# RP_INTERFACE_BOARD_V4_1.net
KiCad netlist of a schematic drawn in Altium Designer
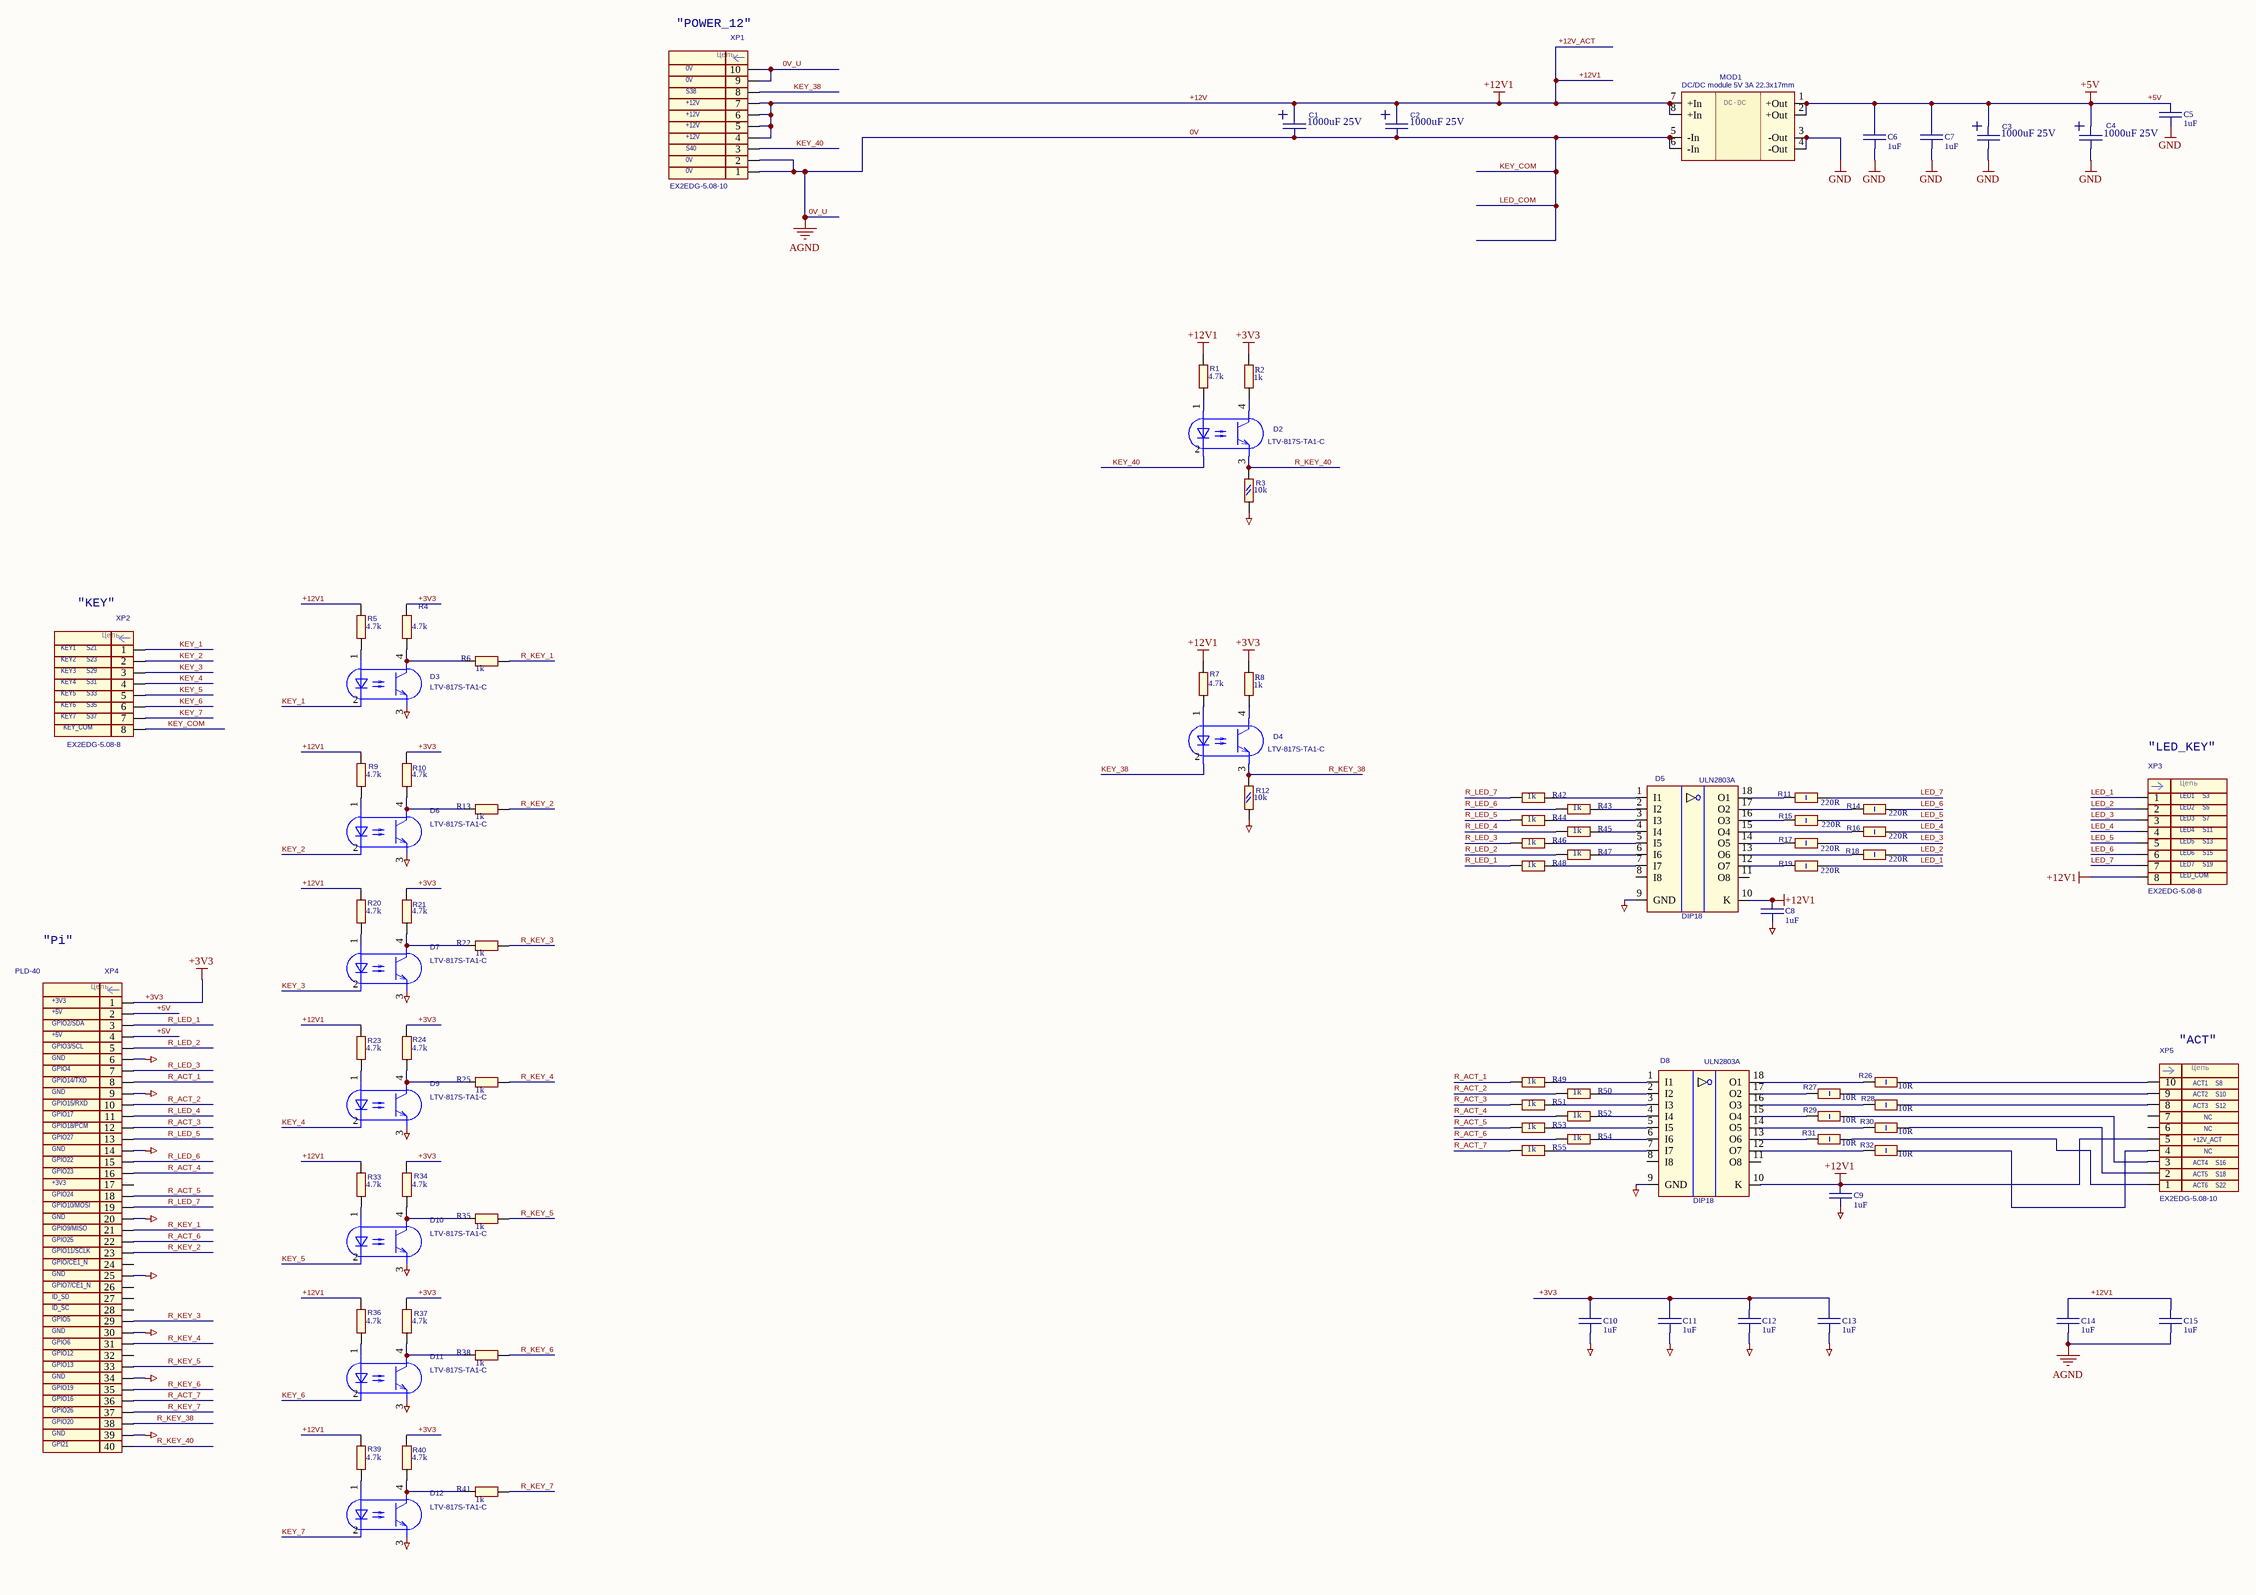
[diagram p0: RP_INTERFACE_BOARD_V4.1.SchDoc]

(export (version "E")
  (design (tool "Eeschema 10.0.6"))
  (components
    (comp (ref "C1")
      (value "EXR102M25B")
      (footprint "RADIAL 13X25")
      (description "1000uF 25V 13x21mm")
      (fields (field (name "ALTIUM_UNNAMED_1") "1000uF 25V"))
      (libsource (lib "*") (part "EXR102M25B"))
    )
    (comp (ref "C2")
      (value "EXR102M25B")
      (footprint "RADIAL 13X25")
      (description "1000uF 25V 13x21mm")
      (fields (field (name "ALTIUM_UNNAMED_1") "1000uF 25V"))
      (libsource (lib "RP_INTERFACE_BOARD") (part "EXR102M25B"))
    )
    (comp (ref "C3")
      (value "EXR102M25B")
      (footprint "RADIAL 13X25")
      (description "1000uF 25V 13x21mm")
      (fields (field (name "ALTIUM_UNNAMED_1") "1000uF 25V"))
      (libsource (lib "RP_INTERFACE_BOARD") (part "EXR102M25B"))
    )
    (comp (ref "C4")
      (value "EXR102M25B")
      (footprint "RADIAL 13X25")
      (description "1000uF 25V 13x21mm")
      (fields (field (name "ALTIUM_UNNAMED_1") "1000uF 25V"))
      (libsource (lib "RP_INTERFACE_BOARD") (part "EXR102M25B"))
    )
    (comp (ref "C5")
      (value "C0805, 1uF, 50V, X7R")
      (footprint "C0805")
      (fields (field (name "ALTIUM_UNNAMED_1") "1uF"))
      (libsource (lib "CAPACITORS") (part "C0805, 1uF, 50V, X7R"))
    )
    (comp (ref "C6")
      (value "C0805, 1uF, 50V, X7R")
      (footprint "C0805")
      (fields (field (name "ALTIUM_UNNAMED_1") "1uF"))
      (libsource (lib "CAPACITORS") (part "C0805, 1uF, 50V, X7R"))
    )
    (comp (ref "C7")
      (value "C0805, 1uF, 50V, X7R")
      (footprint "C0805")
      (fields (field (name "ALTIUM_UNNAMED_1") "1uF"))
      (libsource (lib "CAPACITORS") (part "C0805, 1uF, 50V, X7R"))
    )
    (comp (ref "C8")
      (value "C0805, 1uF, 50V, X7R")
      (footprint "C0805")
      (fields (field (name "ALTIUM_UNNAMED_1") "1uF"))
      (libsource (lib "CAPACITORS") (part "C0805, 1uF, 50V, X7R"))
    )
    (comp (ref "C9")
      (value "C0805, 1uF, 50V, X7R")
      (footprint "C0805")
      (fields (field (name "ALTIUM_UNNAMED_1") "1uF"))
      (libsource (lib "CAPACITORS") (part "C0805, 1uF, 50V, X7R"))
    )
    (comp (ref "C10")
      (value "C0805, 1uF, 50V, X7R")
      (footprint "C0805")
      (fields (field (name "ALTIUM_UNNAMED_1") "1uF"))
      (libsource (lib "CAPACITORS") (part "C0805, 1uF, 50V, X7R"))
    )
    (comp (ref "C11")
      (value "C0805, 1uF, 50V, X7R")
      (footprint "C0805")
      (fields (field (name "ALTIUM_UNNAMED_1") "1uF"))
      (libsource (lib "CAPACITORS") (part "C0805, 1uF, 50V, X7R"))
    )
    (comp (ref "C12")
      (value "C0805, 1uF, 50V, X7R")
      (footprint "C0805")
      (fields (field (name "ALTIUM_UNNAMED_1") "1uF"))
      (libsource (lib "CAPACITORS") (part "C0805, 1uF, 50V, X7R"))
    )
    (comp (ref "C13")
      (value "C0805, 1uF, 50V, X7R")
      (footprint "C0805")
      (fields (field (name "ALTIUM_UNNAMED_1") "1uF"))
      (libsource (lib "CAPACITORS") (part "C0805, 1uF, 50V, X7R"))
    )
    (comp (ref "C14")
      (value "C0805, 1uF, 50V, X7R")
      (footprint "C0805")
      (fields (field (name "ALTIUM_UNNAMED_1") "1uF"))
      (libsource (lib "CAPACITORS") (part "C0805, 1uF, 50V, X7R"))
    )
    (comp (ref "C15")
      (value "C0805, 1uF, 50V, X7R")
      (footprint "C0805")
      (fields (field (name "ALTIUM_UNNAMED_1") "1uF"))
      (libsource (lib "CAPACITORS") (part "C0805, 1uF, 50V, X7R"))
    )
    (comp (ref "D2")
      (value "LTV-817S-TA1-C")
      (footprint "SOIC4")
      (description "Optoisolator Transistor Output 5000Vrms 1 Channel 4-SMD")
      (libsource (lib "RP_INTERFACE_BOARD") (part "LTV-817S-TA1-C"))
    )
    (comp (ref "D3")
      (value "LTV-817S-TA1-C")
      (footprint "SOIC4")
      (description "Optoisolator Transistor Output 5000Vrms 1 Channel 4-SMD")
      (libsource (lib "RP_INTERFACE_BOARD") (part "LTV-817S-TA1-C"))
    )
    (comp (ref "D4")
      (value "LTV-817S-TA1-C")
      (footprint "SOIC4")
      (description "Optoisolator Transistor Output 5000Vrms 1 Channel 4-SMD")
      (libsource (lib "RP_INTERFACE_BOARD") (part "LTV-817S-TA1-C"))
    )
    (comp (ref "D5")
      (value "ULN2803A")
      (footprint "DIP18_DIP762W46P254L2286H533Q18P")
      (description "Eight Darlington array, DIP-18")
      (fields (field (name "KORPUS3") "DIP18"))
      (libsource (lib "RP_INTERFACE_BOARD") (part "ULN2803A"))
    )
    (comp (ref "D6")
      (value "LTV-817S-TA1-C")
      (footprint "SOIC4")
      (description "Optoisolator Transistor Output 5000Vrms 1 Channel 4-SMD")
      (libsource (lib "RP_INTERFACE_BOARD") (part "LTV-817S-TA1-C"))
    )
    (comp (ref "D7")
      (value "LTV-817S-TA1-C")
      (footprint "SOIC4")
      (description "Optoisolator Transistor Output 5000Vrms 1 Channel 4-SMD")
      (libsource (lib "RP_INTERFACE_BOARD") (part "LTV-817S-TA1-C"))
    )
    (comp (ref "D8")
      (value "ULN2803A")
      (footprint "DIP18_DIP762W46P254L2286H533Q18P")
      (description "Eight Darlington array, DIP-18")
      (fields (field (name "KORPUS3") "DIP18"))
      (libsource (lib "RP_INTERFACE_BOARD") (part "ULN2803A"))
    )
    (comp (ref "D9")
      (value "LTV-817S-TA1-C")
      (footprint "SOIC4")
      (description "Optoisolator Transistor Output 5000Vrms 1 Channel 4-SMD")
      (libsource (lib "RP_INTERFACE_BOARD") (part "LTV-817S-TA1-C"))
    )
    (comp (ref "D10")
      (value "LTV-817S-TA1-C")
      (footprint "SOIC4")
      (description "Optoisolator Transistor Output 5000Vrms 1 Channel 4-SMD")
      (libsource (lib "RP_INTERFACE_BOARD") (part "LTV-817S-TA1-C"))
    )
    (comp (ref "D11")
      (value "LTV-817S-TA1-C")
      (footprint "SOIC4")
      (description "Optoisolator Transistor Output 5000Vrms 1 Channel 4-SMD")
      (libsource (lib "RP_INTERFACE_BOARD") (part "LTV-817S-TA1-C"))
    )
    (comp (ref "D12")
      (value "LTV-817S-TA1-C")
      (footprint "SOIC4")
      (description "Optoisolator Transistor Output 5000Vrms 1 Channel 4-SMD")
      (libsource (lib "RP_INTERFACE_BOARD") (part "LTV-817S-TA1-C"))
    )
    (comp (ref "MOD1")
      (value "DC/DC module 5V 3A 22.3x17mm")
      (footprint "DC_DC_module 5V, 17x22.3mm")
      (libsource (lib "*") (part "DC/DC module 5V 3A 22.3x17mm"))
    )
    (comp (ref "R1")
      (value "4.7k")
      (footprint "R0805")
      (description "R0805, 4.7k, 5%")
      (libsource (lib "RP_INTERFACE_BOARD") (part "R0805, 4.7k, 5%"))
    )
    (comp (ref "R2")
      (value "R0805, 1k, 5%")
      (footprint "R0805")
      (fields (field (name "ALTIUM_UNNAMED_1") "1k"))
      (libsource (lib "") (part "R0805, 1k, 5%_1"))
    )
    (comp (ref "R3")
      (value "10k")
      (footprint "R0805")
      (description "R0805, 10k, 5%")
      (libsource (lib "RP_INTERFACE_BOARD") (part "R0805, 10k, 5%"))
    )
    (comp (ref "R4")
      (value "4.7k")
      (footprint "R0805")
      (description "R0805, 4.7k, 5%")
      (libsource (lib "RP_INTERFACE_BOARD") (part "R0805, 4.7k, 5%"))
    )
    (comp (ref "R5")
      (value "4.7k")
      (footprint "R0805")
      (description "R0805, 4.7k, 5%")
      (libsource (lib "RP_INTERFACE_BOARD") (part "R0805, 4.7k, 5%"))
    )
    (comp (ref "R6")
      (value "R0805, 1k, 5%")
      (footprint "R0805")
      (fields (field (name "ALTIUM_UNNAMED_1") "1k"))
      (libsource (lib "RP_INTERFACE_BOARD") (part "R0805, 1k, 5%"))
    )
    (comp (ref "R7")
      (value "4.7k")
      (footprint "R0805")
      (description "R0805, 4.7k, 5%")
      (libsource (lib "RP_INTERFACE_BOARD") (part "R0805, 4.7k, 5%"))
    )
    (comp (ref "R8")
      (value "R0805, 1k, 5%")
      (footprint "R0805")
      (fields (field (name "ALTIUM_UNNAMED_1") "1k"))
      (libsource (lib "") (part "R0805, 1k, 5%_1"))
    )
    (comp (ref "R9")
      (value "4.7k")
      (footprint "R0805")
      (description "R0805, 4.7k, 5%")
      (libsource (lib "RP_INTERFACE_BOARD") (part "R0805, 4.7k, 5%"))
    )
    (comp (ref "R10")
      (value "4.7k")
      (footprint "R0805")
      (description "R0805, 4.7k, 5%")
      (libsource (lib "RP_INTERFACE_BOARD") (part "R0805, 4.7k, 5%"))
    )
    (comp (ref "R11")
      (value "R1206, 220R, 5%")
      (footprint "R1206")
      (fields (field (name "ALTIUM_UNNAMED_1") "220R"))
      (libsource (lib "RP_INTERFACE_BOARD") (part "R1206, 220R, 5%"))
    )
    (comp (ref "R12")
      (value "10k")
      (footprint "R0805")
      (description "R0805, 10k, 5%")
      (libsource (lib "RP_INTERFACE_BOARD") (part "R0805, 10k, 5%"))
    )
    (comp (ref "R13")
      (value "R0805, 1k, 5%")
      (footprint "R0805")
      (fields (field (name "ALTIUM_UNNAMED_1") "1k"))
      (libsource (lib "RP_INTERFACE_BOARD") (part "R0805, 1k, 5%"))
    )
    (comp (ref "R14")
      (value "R1206, 220R, 5%")
      (footprint "R1206")
      (fields (field (name "ALTIUM_UNNAMED_1") "220R"))
      (libsource (lib "RP_INTERFACE_BOARD") (part "R1206, 220R, 5%"))
    )
    (comp (ref "R15")
      (value "R1206, 220R, 5%")
      (footprint "R1206")
      (fields (field (name "ALTIUM_UNNAMED_1") "220R"))
      (libsource (lib "RP_INTERFACE_BOARD") (part "R1206, 220R, 5%"))
    )
    (comp (ref "R16")
      (value "R1206, 220R, 5%")
      (footprint "R1206")
      (fields (field (name "ALTIUM_UNNAMED_1") "220R"))
      (libsource (lib "RP_INTERFACE_BOARD") (part "R1206, 220R, 5%"))
    )
    (comp (ref "R17")
      (value "R1206, 220R, 5%")
      (footprint "R1206")
      (fields (field (name "ALTIUM_UNNAMED_1") "220R"))
      (libsource (lib "RP_INTERFACE_BOARD") (part "R1206, 220R, 5%"))
    )
    (comp (ref "R18")
      (value "R1206, 220R, 5%")
      (footprint "R1206")
      (fields (field (name "ALTIUM_UNNAMED_1") "220R"))
      (libsource (lib "RP_INTERFACE_BOARD") (part "R1206, 220R, 5%"))
    )
    (comp (ref "R19")
      (value "R1206, 220R, 5%")
      (footprint "R1206")
      (fields (field (name "ALTIUM_UNNAMED_1") "220R"))
      (libsource (lib "RP_INTERFACE_BOARD") (part "R1206, 220R, 5%"))
    )
    (comp (ref "R20")
      (value "4.7k")
      (footprint "R0805")
      (description "R0805, 4.7k, 5%")
      (libsource (lib "RP_INTERFACE_BOARD") (part "R0805, 4.7k, 5%"))
    )
    (comp (ref "R21")
      (value "4.7k")
      (footprint "R0805")
      (description "R0805, 4.7k, 5%")
      (libsource (lib "RP_INTERFACE_BOARD") (part "R0805, 4.7k, 5%"))
    )
    (comp (ref "R22")
      (value "R0805, 1k, 5%")
      (footprint "R0805")
      (fields (field (name "ALTIUM_UNNAMED_1") "1k"))
      (libsource (lib "RP_INTERFACE_BOARD") (part "R0805, 1k, 5%"))
    )
    (comp (ref "R23")
      (value "4.7k")
      (footprint "R0805")
      (description "R0805, 4.7k, 5%")
      (libsource (lib "RP_INTERFACE_BOARD") (part "R0805, 4.7k, 5%"))
    )
    (comp (ref "R24")
      (value "4.7k")
      (footprint "R0805")
      (description "R0805, 4.7k, 5%")
      (libsource (lib "RP_INTERFACE_BOARD") (part "R0805, 4.7k, 5%"))
    )
    (comp (ref "R25")
      (value "R0805, 1k, 5%")
      (footprint "R0805")
      (fields (field (name "ALTIUM_UNNAMED_1") "1k"))
      (libsource (lib "RP_INTERFACE_BOARD") (part "R0805, 1k, 5%"))
    )
    (comp (ref "R26")
      (value "R1206, 10R, 5%")
      (footprint "R1206")
      (fields (field (name "ALTIUM_UNNAMED_1") "10R"))
      (libsource (lib "*") (part "R1206, 10R, 5%"))
    )
    (comp (ref "R27")
      (value "R1206, 10R, 5%")
      (footprint "R1206")
      (fields (field (name "ALTIUM_UNNAMED_1") "10R"))
      (libsource (lib "*") (part "R1206, 10R, 5%"))
    )
    (comp (ref "R28")
      (value "R1206, 10R, 5%")
      (footprint "R1206")
      (fields (field (name "ALTIUM_UNNAMED_1") "10R"))
      (libsource (lib "*") (part "R1206, 10R, 5%"))
    )
    (comp (ref "R29")
      (value "R1206, 10R, 5%")
      (footprint "R1206")
      (fields (field (name "ALTIUM_UNNAMED_1") "10R"))
      (libsource (lib "*") (part "R1206, 10R, 5%"))
    )
    (comp (ref "R30")
      (value "R1206, 10R, 5%")
      (footprint "R1206")
      (fields (field (name "ALTIUM_UNNAMED_1") "10R"))
      (libsource (lib "*") (part "R1206, 10R, 5%"))
    )
    (comp (ref "R31")
      (value "R1206, 10R, 5%")
      (footprint "R1206")
      (fields (field (name "ALTIUM_UNNAMED_1") "10R"))
      (libsource (lib "*") (part "R1206, 10R, 5%"))
    )
    (comp (ref "R32")
      (value "R1206, 10R, 5%")
      (footprint "R1206")
      (fields (field (name "ALTIUM_UNNAMED_1") "10R"))
      (libsource (lib "*") (part "R1206, 10R, 5%"))
    )
    (comp (ref "R33")
      (value "4.7k")
      (footprint "R0805")
      (description "R0805, 4.7k, 5%")
      (libsource (lib "RP_INTERFACE_BOARD") (part "R0805, 4.7k, 5%"))
    )
    (comp (ref "R34")
      (value "4.7k")
      (footprint "R0805")
      (description "R0805, 4.7k, 5%")
      (libsource (lib "RP_INTERFACE_BOARD") (part "R0805, 4.7k, 5%"))
    )
    (comp (ref "R35")
      (value "R0805, 1k, 5%")
      (footprint "R0805")
      (fields (field (name "ALTIUM_UNNAMED_1") "1k"))
      (libsource (lib "RP_INTERFACE_BOARD") (part "R0805, 1k, 5%"))
    )
    (comp (ref "R36")
      (value "4.7k")
      (footprint "R0805")
      (description "R0805, 4.7k, 5%")
      (libsource (lib "RP_INTERFACE_BOARD") (part "R0805, 4.7k, 5%"))
    )
    (comp (ref "R37")
      (value "4.7k")
      (footprint "R0805")
      (description "R0805, 4.7k, 5%")
      (libsource (lib "RP_INTERFACE_BOARD") (part "R0805, 4.7k, 5%"))
    )
    (comp (ref "R38")
      (value "R0805, 1k, 5%")
      (footprint "R0805")
      (fields (field (name "ALTIUM_UNNAMED_1") "1k"))
      (libsource (lib "RP_INTERFACE_BOARD") (part "R0805, 1k, 5%"))
    )
    (comp (ref "R39")
      (value "4.7k")
      (footprint "R0805")
      (description "R0805, 4.7k, 5%")
      (libsource (lib "RP_INTERFACE_BOARD") (part "R0805, 4.7k, 5%"))
    )
    (comp (ref "R40")
      (value "4.7k")
      (footprint "R0805")
      (description "R0805, 4.7k, 5%")
      (libsource (lib "RP_INTERFACE_BOARD") (part "R0805, 4.7k, 5%"))
    )
    (comp (ref "R41")
      (value "R0805, 1k, 5%")
      (footprint "R0805")
      (fields (field (name "ALTIUM_UNNAMED_1") "1k"))
      (libsource (lib "RP_INTERFACE_BOARD") (part "R0805, 1k, 5%"))
    )
    (comp (ref "R42")
      (value "R0805, 1k, 5%")
      (footprint "R0805")
      (fields (field (name "ALTIUM_UNNAMED_1") "1k"))
      (libsource (lib "RP_INTERFACE_BOARD") (part "R0805, 1k, 5%"))
    )
    (comp (ref "R43")
      (value "R0805, 1k, 5%")
      (footprint "R0805")
      (fields (field (name "ALTIUM_UNNAMED_1") "1k"))
      (libsource (lib "RP_INTERFACE_BOARD") (part "R0805, 1k, 5%"))
    )
    (comp (ref "R44")
      (value "R0805, 1k, 5%")
      (footprint "R0805")
      (fields (field (name "ALTIUM_UNNAMED_1") "1k"))
      (libsource (lib "RP_INTERFACE_BOARD") (part "R0805, 1k, 5%"))
    )
    (comp (ref "R45")
      (value "R0805, 1k, 5%")
      (footprint "R0805")
      (fields (field (name "ALTIUM_UNNAMED_1") "1k"))
      (libsource (lib "RP_INTERFACE_BOARD") (part "R0805, 1k, 5%"))
    )
    (comp (ref "R46")
      (value "R0805, 1k, 5%")
      (footprint "R0805")
      (fields (field (name "ALTIUM_UNNAMED_1") "1k"))
      (libsource (lib "RP_INTERFACE_BOARD") (part "R0805, 1k, 5%"))
    )
    (comp (ref "R47")
      (value "R0805, 1k, 5%")
      (footprint "R0805")
      (fields (field (name "ALTIUM_UNNAMED_1") "1k"))
      (libsource (lib "RP_INTERFACE_BOARD") (part "R0805, 1k, 5%"))
    )
    (comp (ref "R48")
      (value "R0805, 1k, 5%")
      (footprint "R0805")
      (fields (field (name "ALTIUM_UNNAMED_1") "1k"))
      (libsource (lib "RP_INTERFACE_BOARD") (part "R0805, 1k, 5%"))
    )
    (comp (ref "R49")
      (value "R0805, 1k, 5%")
      (footprint "R0805")
      (fields (field (name "ALTIUM_UNNAMED_1") "1k"))
      (libsource (lib "RP_INTERFACE_BOARD") (part "R0805, 1k, 5%"))
    )
    (comp (ref "R50")
      (value "R0805, 1k, 5%")
      (footprint "R0805")
      (fields (field (name "ALTIUM_UNNAMED_1") "1k"))
      (libsource (lib "RP_INTERFACE_BOARD") (part "R0805, 1k, 5%"))
    )
    (comp (ref "R51")
      (value "R0805, 1k, 5%")
      (footprint "R0805")
      (fields (field (name "ALTIUM_UNNAMED_1") "1k"))
      (libsource (lib "RP_INTERFACE_BOARD") (part "R0805, 1k, 5%"))
    )
    (comp (ref "R52")
      (value "R0805, 1k, 5%")
      (footprint "R0805")
      (fields (field (name "ALTIUM_UNNAMED_1") "1k"))
      (libsource (lib "RP_INTERFACE_BOARD") (part "R0805, 1k, 5%"))
    )
    (comp (ref "R53")
      (value "R0805, 1k, 5%")
      (footprint "R0805")
      (fields (field (name "ALTIUM_UNNAMED_1") "1k"))
      (libsource (lib "RP_INTERFACE_BOARD") (part "R0805, 1k, 5%"))
    )
    (comp (ref "R54")
      (value "R0805, 1k, 5%")
      (footprint "R0805")
      (fields (field (name "ALTIUM_UNNAMED_1") "1k"))
      (libsource (lib "RP_INTERFACE_BOARD") (part "R0805, 1k, 5%"))
    )
    (comp (ref "R55")
      (value "R0805, 1k, 5%")
      (footprint "R0805")
      (fields (field (name "ALTIUM_UNNAMED_1") "1k"))
      (libsource (lib "RP_INTERFACE_BOARD") (part "R0805, 1k, 5%"))
    )
    (comp (ref "XP1")
      (value "EX2EDG-5.08-10")
      (footprint "5P08-10N")
      (libsource (lib "") (part "EX2EDG-5_0.08-10_1"))
    )
    (comp (ref "XP2")
      (value "EX2EDG-5.08-8")
      (footprint "5P08-8N")
      (libsource (lib "*") (part "EX2EDG-5.08-8"))
    )
    (comp (ref "XP3")
      (value "EX2EDG-5.08-8")
      (footprint "5P08-8N")
      (libsource (lib "") (part "EX2EDG-5.08-8_1"))
    )
    (comp (ref "XP4")
      (value "PLD-40")
      (footprint "PLD-40")
      (description "PLD-40, вилка штыревая 2.54мм 2x20 прямая")
      (libsource (lib "*") (part "PLD-40"))
    )
    (comp (ref "XP5")
      (value "EX2EDG-5.08-10")
      (footprint "5P08-10N")
      (libsource (lib "*") (part "EX2EDG-5_0.08-10"))
    )
  )
  (nets
    (net (code "1") (name "+3V3") (class "Default")
      (node (ref "C10") (pin "1") (pintype "passive"))
      (node (ref "C11") (pin "1") (pintype "passive"))
      (node (ref "C12") (pin "1") (pintype "passive"))
      (node (ref "C13") (pin "1") (pintype "passive"))
      (node (ref "R10") (pin "1") (pinfunction "1_1") (pintype "passive"))
      (node (ref "R2") (pin "1") (pinfunction "1_1") (pintype "passive"))
      (node (ref "R21") (pin "1") (pinfunction "1_1") (pintype "passive"))
      (node (ref "R24") (pin "1") (pinfunction "1_1") (pintype "passive"))
      (node (ref "R34") (pin "1") (pinfunction "1_1") (pintype "passive"))
      (node (ref "R37") (pin "1") (pinfunction "1_1") (pintype "passive"))
      (node (ref "R4") (pin "1") (pinfunction "1_1") (pintype "passive"))
      (node (ref "R40") (pin "1") (pinfunction "1_1") (pintype "passive"))
      (node (ref "R8") (pin "1") (pinfunction "1_1") (pintype "passive"))
      (node (ref "XP4") (pin "1") (pinfunction "1_1") (pintype "passive"))
    )
    (net (code "2") (name "+5V") (class "Default")
      (node (ref "C3") (pin "2") (pintype "passive"))
      (node (ref "C4") (pin "2") (pintype "passive"))
      (node (ref "C5") (pin "1") (pintype "passive"))
      (node (ref "C6") (pin "1") (pintype "passive"))
      (node (ref "C7") (pin "1") (pintype "passive"))
      (node (ref "MOD1") (pin "1") (pinfunction "+Out_1") (pintype "power_in"))
      (node (ref "MOD1") (pin "2") (pinfunction "+Out_2") (pintype "power_in"))
      (node (ref "XP4") (pin "2") (pinfunction "2_2") (pintype "passive"))
      (node (ref "XP4") (pin "4") (pinfunction "4_4") (pintype "passive"))
    )
    (net (code "3") (name "+12V1") (class "Default")
      (node (ref "C1") (pin "2") (pintype "passive"))
      (node (ref "C14") (pin "1") (pintype "passive"))
      (node (ref "C15") (pin "1") (pintype "passive"))
      (node (ref "C2") (pin "2") (pintype "passive"))
      (node (ref "C8") (pin "1") (pintype "passive"))
      (node (ref "C9") (pin "1") (pintype "passive"))
      (node (ref "D5") (pin "10") (pinfunction "K_10") (pintype "power_in"))
      (node (ref "D8") (pin "10") (pinfunction "K_10") (pintype "power_in"))
      (node (ref "MOD1") (pin "7") (pinfunction "+In_7") (pintype "power_in"))
      (node (ref "MOD1") (pin "8") (pinfunction "+In_8") (pintype "power_in"))
      (node (ref "R1") (pin "1") (pinfunction "1_1") (pintype "passive"))
      (node (ref "R20") (pin "1") (pinfunction "1_1") (pintype "passive"))
      (node (ref "R23") (pin "1") (pinfunction "1_1") (pintype "passive"))
      (node (ref "R33") (pin "1") (pinfunction "1_1") (pintype "passive"))
      (node (ref "R36") (pin "1") (pinfunction "1_1") (pintype "passive"))
      (node (ref "R39") (pin "1") (pinfunction "1_1") (pintype "passive"))
      (node (ref "R5") (pin "1") (pinfunction "1_1") (pintype "passive"))
      (node (ref "R7") (pin "1") (pinfunction "1_1") (pintype "passive"))
      (node (ref "R9") (pin "1") (pinfunction "1_1") (pintype "passive"))
      (node (ref "XP1") (pin "4") (pinfunction "4_4") (pintype "passive"))
      (node (ref "XP1") (pin "5") (pinfunction "5_5") (pintype "passive"))
      (node (ref "XP1") (pin "6") (pinfunction "6_6") (pintype "passive"))
      (node (ref "XP1") (pin "7") (pinfunction "7_7") (pintype "passive"))
      (node (ref "XP3") (pin "8") (pinfunction "8_8") (pintype "passive"))
      (node (ref "XP5") (pin "5") (pinfunction "5_5") (pintype "passive"))
    )
    (net (code "4") (name "/KEY_1") (class "Default")
      (node (ref "D3") (pin "2") (pinfunction "2_2") (pintype "passive"))
      (node (ref "XP2") (pin "1") (pinfunction "1_1") (pintype "passive"))
    )
    (net (code "5") (name "/KEY_2") (class "Default")
      (node (ref "D6") (pin "2") (pinfunction "2_2") (pintype "passive"))
      (node (ref "XP2") (pin "2") (pinfunction "2_2") (pintype "passive"))
    )
    (net (code "6") (name "/KEY_3") (class "Default")
      (node (ref "D7") (pin "2") (pinfunction "2_2") (pintype "passive"))
      (node (ref "XP2") (pin "3") (pinfunction "3_3") (pintype "passive"))
    )
    (net (code "7") (name "/KEY_4") (class "Default")
      (node (ref "D9") (pin "2") (pinfunction "2_2") (pintype "passive"))
      (node (ref "XP2") (pin "4") (pinfunction "4_4") (pintype "passive"))
    )
    (net (code "8") (name "/KEY_5") (class "Default")
      (node (ref "D10") (pin "2") (pinfunction "2_2") (pintype "passive"))
      (node (ref "XP2") (pin "5") (pinfunction "5_5") (pintype "passive"))
    )
    (net (code "9") (name "/KEY_6") (class "Default")
      (node (ref "D11") (pin "2") (pinfunction "2_2") (pintype "passive"))
      (node (ref "XP2") (pin "6") (pinfunction "6_6") (pintype "passive"))
    )
    (net (code "10") (name "/KEY_7") (class "Default")
      (node (ref "D12") (pin "2") (pinfunction "2_2") (pintype "passive"))
      (node (ref "XP2") (pin "7") (pinfunction "7_7") (pintype "passive"))
    )
    (net (code "11") (name "/KEY_38") (class "Default")
      (node (ref "D4") (pin "2") (pinfunction "2_2") (pintype "passive"))
      (node (ref "XP1") (pin "8") (pinfunction "8_8") (pintype "passive"))
    )
    (net (code "12") (name "/KEY_40") (class "Default")
      (node (ref "D2") (pin "2") (pinfunction "2_2") (pintype "passive"))
      (node (ref "XP1") (pin "3") (pinfunction "3_3") (pintype "passive"))
    )
    (net (code "13") (name "/LED_1") (class "Default")
      (node (ref "R19") (pin "2") (pinfunction "2_2") (pintype "passive"))
      (node (ref "XP3") (pin "1") (pinfunction "1_1") (pintype "passive"))
    )
    (net (code "14") (name "/LED_2") (class "Default")
      (node (ref "R18") (pin "2") (pinfunction "2_2") (pintype "passive"))
      (node (ref "XP3") (pin "2") (pinfunction "2_2") (pintype "passive"))
    )
    (net (code "15") (name "/LED_3") (class "Default")
      (node (ref "R17") (pin "2") (pinfunction "2_2") (pintype "passive"))
      (node (ref "XP3") (pin "3") (pinfunction "3_3") (pintype "passive"))
    )
    (net (code "16") (name "/LED_4") (class "Default")
      (node (ref "R16") (pin "2") (pinfunction "2_2") (pintype "passive"))
      (node (ref "XP3") (pin "4") (pinfunction "4_4") (pintype "passive"))
    )
    (net (code "17") (name "/LED_5") (class "Default")
      (node (ref "R15") (pin "2") (pinfunction "2_2") (pintype "passive"))
      (node (ref "XP3") (pin "5") (pinfunction "5_5") (pintype "passive"))
    )
    (net (code "18") (name "/LED_6") (class "Default")
      (node (ref "R14") (pin "2") (pinfunction "2_2") (pintype "passive"))
      (node (ref "XP3") (pin "6") (pinfunction "6_6") (pintype "passive"))
    )
    (net (code "19") (name "/LED_7") (class "Default")
      (node (ref "R11") (pin "2") (pinfunction "2_2") (pintype "passive"))
      (node (ref "XP3") (pin "7") (pinfunction "7_7") (pintype "passive"))
    )
    (net (code "20") (name "/R_ACT_1") (class "Default")
      (node (ref "R49") (pin "2") (pinfunction "2_2") (pintype "passive"))
      (node (ref "XP4") (pin "8") (pinfunction "8_8") (pintype "passive"))
    )
    (net (code "21") (name "/R_ACT_2") (class "Default")
      (node (ref "R50") (pin "2") (pinfunction "2_2") (pintype "passive"))
      (node (ref "XP4") (pin "10") (pinfunction "10_10") (pintype "passive"))
    )
    (net (code "22") (name "/R_ACT_3") (class "Default")
      (node (ref "R51") (pin "2") (pinfunction "2_2") (pintype "passive"))
      (node (ref "XP4") (pin "12") (pinfunction "12_12") (pintype "passive"))
    )
    (net (code "23") (name "/R_ACT_4") (class "Default")
      (node (ref "R52") (pin "2") (pinfunction "2_2") (pintype "passive"))
      (node (ref "XP4") (pin "16") (pinfunction "16_16") (pintype "passive"))
    )
    (net (code "24") (name "/R_ACT_5") (class "Default")
      (node (ref "R53") (pin "2") (pinfunction "2_2") (pintype "passive"))
      (node (ref "XP4") (pin "18") (pinfunction "18_18") (pintype "passive"))
    )
    (net (code "25") (name "/R_ACT_6") (class "Default")
      (node (ref "R54") (pin "2") (pinfunction "2_2") (pintype "passive"))
      (node (ref "XP4") (pin "22") (pinfunction "22_22") (pintype "passive"))
    )
    (net (code "26") (name "/R_ACT_7") (class "Default")
      (node (ref "R55") (pin "2") (pinfunction "2_2") (pintype "passive"))
      (node (ref "XP4") (pin "36") (pinfunction "36_36") (pintype "passive"))
    )
    (net (code "27") (name "/R_KEY_1") (class "Default")
      (node (ref "R6") (pin "1") (pinfunction "1_1") (pintype "passive"))
      (node (ref "XP4") (pin "21") (pinfunction "21_21") (pintype "passive"))
    )
    (net (code "28") (name "/R_KEY_2") (class "Default")
      (node (ref "R13") (pin "1") (pinfunction "1_1") (pintype "passive"))
      (node (ref "XP4") (pin "23") (pinfunction "23_23") (pintype "passive"))
    )
    (net (code "29") (name "/R_KEY_3") (class "Default")
      (node (ref "R22") (pin "1") (pinfunction "1_1") (pintype "passive"))
      (node (ref "XP4") (pin "29") (pinfunction "29_29") (pintype "passive"))
    )
    (net (code "30") (name "/R_KEY_4") (class "Default")
      (node (ref "R25") (pin "1") (pinfunction "1_1") (pintype "passive"))
      (node (ref "XP4") (pin "31") (pinfunction "31_31") (pintype "passive"))
    )
    (net (code "31") (name "/R_KEY_5") (class "Default")
      (node (ref "R35") (pin "1") (pinfunction "1_1") (pintype "passive"))
      (node (ref "XP4") (pin "33") (pinfunction "33_33") (pintype "passive"))
    )
    (net (code "32") (name "/R_KEY_6") (class "Default")
      (node (ref "R38") (pin "1") (pinfunction "1_1") (pintype "passive"))
      (node (ref "XP4") (pin "35") (pinfunction "35_35") (pintype "passive"))
    )
    (net (code "33") (name "/R_KEY_7") (class "Default")
      (node (ref "R41") (pin "1") (pinfunction "1_1") (pintype "passive"))
      (node (ref "XP4") (pin "37") (pinfunction "37_37") (pintype "passive"))
    )
    (net (code "34") (name "/R_KEY_38") (class "Default")
      (node (ref "D4") (pin "3") (pinfunction "3_3") (pintype "passive"))
      (node (ref "R12") (pin "1") (pinfunction "1_1") (pintype "passive"))
      (node (ref "XP4") (pin "38") (pinfunction "38_38") (pintype "passive"))
    )
    (net (code "35") (name "/R_KEY_40") (class "Default")
      (node (ref "D2") (pin "3") (pinfunction "3_3") (pintype "passive"))
      (node (ref "R3") (pin "1") (pinfunction "1_1") (pintype "passive"))
      (node (ref "XP4") (pin "40") (pinfunction "40_40") (pintype "passive"))
    )
    (net (code "36") (name "/R_LED_1") (class "Default")
      (node (ref "R48") (pin "2") (pinfunction "2_2") (pintype "passive"))
      (node (ref "XP4") (pin "3") (pinfunction "3_3") (pintype "passive"))
    )
    (net (code "37") (name "/R_LED_2") (class "Default")
      (node (ref "R47") (pin "2") (pinfunction "2_2") (pintype "passive"))
      (node (ref "XP4") (pin "5") (pinfunction "5_5") (pintype "passive"))
    )
    (net (code "38") (name "/R_LED_3") (class "Default")
      (node (ref "R46") (pin "2") (pinfunction "2_2") (pintype "passive"))
      (node (ref "XP4") (pin "7") (pinfunction "7_7") (pintype "passive"))
    )
    (net (code "39") (name "/R_LED_4") (class "Default")
      (node (ref "R45") (pin "2") (pinfunction "2_2") (pintype "passive"))
      (node (ref "XP4") (pin "11") (pinfunction "11_11") (pintype "passive"))
    )
    (net (code "40") (name "/R_LED_5") (class "Default")
      (node (ref "R44") (pin "2") (pinfunction "2_2") (pintype "passive"))
      (node (ref "XP4") (pin "13") (pinfunction "13_13") (pintype "passive"))
    )
    (net (code "41") (name "/R_LED_6") (class "Default")
      (node (ref "R43") (pin "2") (pinfunction "2_2") (pintype "passive"))
      (node (ref "XP4") (pin "15") (pinfunction "15_15") (pintype "passive"))
    )
    (net (code "42") (name "/R_LED_7") (class "Default")
      (node (ref "R42") (pin "2") (pinfunction "2_2") (pintype "passive"))
      (node (ref "XP4") (pin "19") (pinfunction "19_19") (pintype "passive"))
    )
    (net (code "43") (name "AGND") (class "Default")
      (node (ref "C1") (pin "1") (pintype "passive"))
      (node (ref "C14") (pin "2") (pintype "passive"))
      (node (ref "C15") (pin "2") (pintype "passive"))
      (node (ref "C2") (pin "1") (pintype "passive"))
      (node (ref "MOD1") (pin "5") (pinfunction "-In_5") (pintype "power_in"))
      (node (ref "MOD1") (pin "6") (pinfunction "-In_6") (pintype "power_in"))
      (node (ref "XP1") (pin "1") (pinfunction "1_1") (pintype "passive"))
      (node (ref "XP1") (pin "10") (pinfunction "10_10") (pintype "passive"))
      (node (ref "XP1") (pin "2") (pinfunction "2_2") (pintype "passive"))
      (node (ref "XP1") (pin "9") (pinfunction "9_9") (pintype "passive"))
      (node (ref "XP2") (pin "8") (pinfunction "8_8") (pintype "passive"))
    )
    (net (code "44") (name "GND") (class "Default")
      (node (ref "C10") (pin "2") (pintype "passive"))
      (node (ref "C11") (pin "2") (pintype "passive"))
      (node (ref "C12") (pin "2") (pintype "passive"))
      (node (ref "C13") (pin "2") (pintype "passive"))
      (node (ref "C3") (pin "1") (pintype "passive"))
      (node (ref "C4") (pin "1") (pintype "passive"))
      (node (ref "C5") (pin "2") (pintype "passive"))
      (node (ref "C6") (pin "2") (pintype "passive"))
      (node (ref "C7") (pin "2") (pintype "passive"))
      (node (ref "C8") (pin "2") (pintype "passive"))
      (node (ref "C9") (pin "2") (pintype "passive"))
      (node (ref "D10") (pin "3") (pinfunction "3_3") (pintype "passive"))
      (node (ref "D11") (pin "3") (pinfunction "3_3") (pintype "passive"))
      (node (ref "D12") (pin "3") (pinfunction "3_3") (pintype "passive"))
      (node (ref "D3") (pin "3") (pinfunction "3_3") (pintype "passive"))
      (node (ref "D5") (pin "9") (pinfunction "GND_9") (pintype "power_in"))
      (node (ref "D6") (pin "3") (pinfunction "3_3") (pintype "passive"))
      (node (ref "D7") (pin "3") (pinfunction "3_3") (pintype "passive"))
      (node (ref "D8") (pin "9") (pinfunction "GND_9") (pintype "power_in"))
      (node (ref "D9") (pin "3") (pinfunction "3_3") (pintype "passive"))
      (node (ref "MOD1") (pin "3") (pinfunction "-Out_3") (pintype "power_in"))
      (node (ref "MOD1") (pin "4") (pinfunction "-Out_4") (pintype "power_in"))
      (node (ref "R12") (pin "2") (pinfunction "2_2") (pintype "passive"))
      (node (ref "R3") (pin "2") (pinfunction "2_2") (pintype "passive"))
      (node (ref "XP4") (pin "14") (pinfunction "14_14") (pintype "passive"))
      (node (ref "XP4") (pin "20") (pinfunction "20_20") (pintype "passive"))
      (node (ref "XP4") (pin "25") (pinfunction "25_25") (pintype "passive"))
      (node (ref "XP4") (pin "30") (pinfunction "30_30") (pintype "passive"))
      (node (ref "XP4") (pin "34") (pinfunction "34_34") (pintype "passive"))
      (node (ref "XP4") (pin "39") (pinfunction "39_39") (pintype "passive"))
      (node (ref "XP4") (pin "6") (pinfunction "6_6") (pintype "passive"))
      (node (ref "XP4") (pin "9") (pinfunction "9_9") (pintype "passive"))
    )
    (net (code "45") (name "Net-(D2-Pad1)") (class "Default")
      (node (ref "D2") (pin "1") (pinfunction "1_1") (pintype "passive"))
      (node (ref "R1") (pin "2") (pinfunction "2_2") (pintype "passive"))
    )
    (net (code "46") (name "Net-(D2-Pad4)") (class "Default")
      (node (ref "D2") (pin "4") (pinfunction "4_4") (pintype "passive"))
      (node (ref "R2") (pin "2") (pinfunction "2_2") (pintype "passive"))
    )
    (net (code "47") (name "Net-(D3-Pad1)") (class "Default")
      (node (ref "D3") (pin "1") (pinfunction "1_1") (pintype "passive"))
      (node (ref "R5") (pin "2") (pinfunction "2_2") (pintype "passive"))
    )
    (net (code "48") (name "Net-(D3-Pad4)") (class "Default")
      (node (ref "D3") (pin "4") (pinfunction "4_4") (pintype "passive"))
      (node (ref "R4") (pin "2") (pinfunction "2_2") (pintype "passive"))
      (node (ref "R6") (pin "2") (pinfunction "2_2") (pintype "passive"))
    )
    (net (code "49") (name "Net-(D4-Pad1)") (class "Default")
      (node (ref "D4") (pin "1") (pinfunction "1_1") (pintype "passive"))
      (node (ref "R7") (pin "2") (pinfunction "2_2") (pintype "passive"))
    )
    (net (code "50") (name "Net-(D4-Pad4)") (class "Default")
      (node (ref "D4") (pin "4") (pinfunction "4_4") (pintype "passive"))
      (node (ref "R8") (pin "2") (pinfunction "2_2") (pintype "passive"))
    )
    (net (code "51") (name "Net-(D5-I1)") (class "Default")
      (node (ref "D5") (pin "1") (pinfunction "I1_1") (pintype "passive"))
      (node (ref "R42") (pin "1") (pinfunction "1_1") (pintype "passive"))
    )
    (net (code "52") (name "Net-(D5-I2)") (class "Default")
      (node (ref "D5") (pin "2") (pinfunction "I2_2") (pintype "passive"))
      (node (ref "R43") (pin "1") (pinfunction "1_1") (pintype "passive"))
    )
    (net (code "53") (name "Net-(D5-I3)") (class "Default")
      (node (ref "D5") (pin "3") (pinfunction "I3_3") (pintype "passive"))
      (node (ref "R44") (pin "1") (pinfunction "1_1") (pintype "passive"))
    )
    (net (code "54") (name "Net-(D5-I4)") (class "Default")
      (node (ref "D5") (pin "4") (pinfunction "I4_4") (pintype "passive"))
      (node (ref "R45") (pin "1") (pinfunction "1_1") (pintype "passive"))
    )
    (net (code "55") (name "Net-(D5-I5)") (class "Default")
      (node (ref "D5") (pin "5") (pinfunction "I5_5") (pintype "passive"))
      (node (ref "R46") (pin "1") (pinfunction "1_1") (pintype "passive"))
    )
    (net (code "56") (name "Net-(D5-I6)") (class "Default")
      (node (ref "D5") (pin "6") (pinfunction "I6_6") (pintype "passive"))
      (node (ref "R47") (pin "1") (pinfunction "1_1") (pintype "passive"))
    )
    (net (code "57") (name "Net-(D5-I7)") (class "Default")
      (node (ref "D5") (pin "7") (pinfunction "I7_7") (pintype "passive"))
      (node (ref "R48") (pin "1") (pinfunction "1_1") (pintype "passive"))
    )
    (net (code "58") (name "Net-(D5-O1)") (class "Default")
      (node (ref "D5") (pin "18") (pinfunction "O1_18") (pintype "passive"))
      (node (ref "R11") (pin "1") (pinfunction "1_1") (pintype "passive"))
    )
    (net (code "59") (name "Net-(D5-O2)") (class "Default")
      (node (ref "D5") (pin "17") (pinfunction "O2_17") (pintype "passive"))
      (node (ref "R14") (pin "1") (pinfunction "1_1") (pintype "passive"))
    )
    (net (code "60") (name "Net-(D5-O3)") (class "Default")
      (node (ref "D5") (pin "16") (pinfunction "O3_16") (pintype "passive"))
      (node (ref "R15") (pin "1") (pinfunction "1_1") (pintype "passive"))
    )
    (net (code "61") (name "Net-(D5-O4)") (class "Default")
      (node (ref "D5") (pin "15") (pinfunction "O4_15") (pintype "passive"))
      (node (ref "R16") (pin "1") (pinfunction "1_1") (pintype "passive"))
    )
    (net (code "62") (name "Net-(D5-O5)") (class "Default")
      (node (ref "D5") (pin "14") (pinfunction "O5_14") (pintype "passive"))
      (node (ref "R17") (pin "1") (pinfunction "1_1") (pintype "passive"))
    )
    (net (code "63") (name "Net-(D5-O6)") (class "Default")
      (node (ref "D5") (pin "13") (pinfunction "O6_13") (pintype "passive"))
      (node (ref "R18") (pin "1") (pinfunction "1_1") (pintype "passive"))
    )
    (net (code "64") (name "Net-(D5-O7)") (class "Default")
      (node (ref "D5") (pin "12") (pinfunction "O7_12") (pintype "passive"))
      (node (ref "R19") (pin "1") (pinfunction "1_1") (pintype "passive"))
    )
    (net (code "65") (name "Net-(D6-Pad1)") (class "Default")
      (node (ref "D6") (pin "1") (pinfunction "1_1") (pintype "passive"))
      (node (ref "R9") (pin "2") (pinfunction "2_2") (pintype "passive"))
    )
    (net (code "66") (name "Net-(D6-Pad4)") (class "Default")
      (node (ref "D6") (pin "4") (pinfunction "4_4") (pintype "passive"))
      (node (ref "R10") (pin "2") (pinfunction "2_2") (pintype "passive"))
      (node (ref "R13") (pin "2") (pinfunction "2_2") (pintype "passive"))
    )
    (net (code "67") (name "Net-(D7-Pad1)") (class "Default")
      (node (ref "D7") (pin "1") (pinfunction "1_1") (pintype "passive"))
      (node (ref "R20") (pin "2") (pinfunction "2_2") (pintype "passive"))
    )
    (net (code "68") (name "Net-(D7-Pad4)") (class "Default")
      (node (ref "D7") (pin "4") (pinfunction "4_4") (pintype "passive"))
      (node (ref "R21") (pin "2") (pinfunction "2_2") (pintype "passive"))
      (node (ref "R22") (pin "2") (pinfunction "2_2") (pintype "passive"))
    )
    (net (code "69") (name "Net-(D8-I1)") (class "Default")
      (node (ref "D8") (pin "1") (pinfunction "I1_1") (pintype "passive"))
      (node (ref "R49") (pin "1") (pinfunction "1_1") (pintype "passive"))
    )
    (net (code "70") (name "Net-(D8-I2)") (class "Default")
      (node (ref "D8") (pin "2") (pinfunction "I2_2") (pintype "passive"))
      (node (ref "R50") (pin "1") (pinfunction "1_1") (pintype "passive"))
    )
    (net (code "71") (name "Net-(D8-I3)") (class "Default")
      (node (ref "D8") (pin "3") (pinfunction "I3_3") (pintype "passive"))
      (node (ref "R51") (pin "1") (pinfunction "1_1") (pintype "passive"))
    )
    (net (code "72") (name "Net-(D8-I4)") (class "Default")
      (node (ref "D8") (pin "4") (pinfunction "I4_4") (pintype "passive"))
      (node (ref "R52") (pin "1") (pinfunction "1_1") (pintype "passive"))
    )
    (net (code "73") (name "Net-(D8-I5)") (class "Default")
      (node (ref "D8") (pin "5") (pinfunction "I5_5") (pintype "passive"))
      (node (ref "R53") (pin "1") (pinfunction "1_1") (pintype "passive"))
    )
    (net (code "74") (name "Net-(D8-I6)") (class "Default")
      (node (ref "D8") (pin "6") (pinfunction "I6_6") (pintype "passive"))
      (node (ref "R54") (pin "1") (pinfunction "1_1") (pintype "passive"))
    )
    (net (code "75") (name "Net-(D8-I7)") (class "Default")
      (node (ref "D8") (pin "7") (pinfunction "I7_7") (pintype "passive"))
      (node (ref "R55") (pin "1") (pinfunction "1_1") (pintype "passive"))
    )
    (net (code "76") (name "Net-(D8-O1)") (class "Default")
      (node (ref "D8") (pin "18") (pinfunction "O1_18") (pintype "passive"))
      (node (ref "R26") (pin "2") (pinfunction "2_2") (pintype "passive"))
    )
    (net (code "77") (name "Net-(D8-O2)") (class "Default")
      (node (ref "D8") (pin "17") (pinfunction "O2_17") (pintype "passive"))
      (node (ref "R27") (pin "2") (pinfunction "2_2") (pintype "passive"))
    )
    (net (code "78") (name "Net-(D8-O3)") (class "Default")
      (node (ref "D8") (pin "16") (pinfunction "O3_16") (pintype "passive"))
      (node (ref "R28") (pin "2") (pinfunction "2_2") (pintype "passive"))
    )
    (net (code "79") (name "Net-(D8-O4)") (class "Default")
      (node (ref "D8") (pin "15") (pinfunction "O4_15") (pintype "passive"))
      (node (ref "R29") (pin "2") (pinfunction "2_2") (pintype "passive"))
    )
    (net (code "80") (name "Net-(D8-O5)") (class "Default")
      (node (ref "D8") (pin "14") (pinfunction "O5_14") (pintype "passive"))
      (node (ref "R30") (pin "2") (pinfunction "2_2") (pintype "passive"))
    )
    (net (code "81") (name "Net-(D8-O6)") (class "Default")
      (node (ref "D8") (pin "13") (pinfunction "O6_13") (pintype "passive"))
      (node (ref "R31") (pin "2") (pinfunction "2_2") (pintype "passive"))
    )
    (net (code "82") (name "Net-(D8-O7)") (class "Default")
      (node (ref "D8") (pin "12") (pinfunction "O7_12") (pintype "passive"))
      (node (ref "R32") (pin "2") (pinfunction "2_2") (pintype "passive"))
    )
    (net (code "83") (name "Net-(D9-Pad1)") (class "Default")
      (node (ref "D9") (pin "1") (pinfunction "1_1") (pintype "passive"))
      (node (ref "R23") (pin "2") (pinfunction "2_2") (pintype "passive"))
    )
    (net (code "84") (name "Net-(D9-Pad4)") (class "Default")
      (node (ref "D9") (pin "4") (pinfunction "4_4") (pintype "passive"))
      (node (ref "R24") (pin "2") (pinfunction "2_2") (pintype "passive"))
      (node (ref "R25") (pin "2") (pinfunction "2_2") (pintype "passive"))
    )
    (net (code "85") (name "Net-(D10-Pad1)") (class "Default")
      (node (ref "D10") (pin "1") (pinfunction "1_1") (pintype "passive"))
      (node (ref "R33") (pin "2") (pinfunction "2_2") (pintype "passive"))
    )
    (net (code "86") (name "Net-(D10-Pad4)") (class "Default")
      (node (ref "D10") (pin "4") (pinfunction "4_4") (pintype "passive"))
      (node (ref "R34") (pin "2") (pinfunction "2_2") (pintype "passive"))
      (node (ref "R35") (pin "2") (pinfunction "2_2") (pintype "passive"))
    )
    (net (code "87") (name "Net-(D11-Pad1)") (class "Default")
      (node (ref "D11") (pin "1") (pinfunction "1_1") (pintype "passive"))
      (node (ref "R36") (pin "2") (pinfunction "2_2") (pintype "passive"))
    )
    (net (code "88") (name "Net-(D11-Pad4)") (class "Default")
      (node (ref "D11") (pin "4") (pinfunction "4_4") (pintype "passive"))
      (node (ref "R37") (pin "2") (pinfunction "2_2") (pintype "passive"))
      (node (ref "R38") (pin "2") (pinfunction "2_2") (pintype "passive"))
    )
    (net (code "89") (name "Net-(D12-Pad1)") (class "Default")
      (node (ref "D12") (pin "1") (pinfunction "1_1") (pintype "passive"))
      (node (ref "R39") (pin "2") (pinfunction "2_2") (pintype "passive"))
    )
    (net (code "90") (name "Net-(D12-Pad4)") (class "Default")
      (node (ref "D12") (pin "4") (pinfunction "4_4") (pintype "passive"))
      (node (ref "R40") (pin "2") (pinfunction "2_2") (pintype "passive"))
      (node (ref "R41") (pin "2") (pinfunction "2_2") (pintype "passive"))
    )
    (net (code "91") (name "Net-(R26-Pad1)") (class "Default")
      (node (ref "R26") (pin "1") (pinfunction "1_1") (pintype "passive"))
      (node (ref "XP5") (pin "10") (pinfunction "10_10") (pintype "passive"))
    )
    (net (code "92") (name "Net-(R27-Pad1)") (class "Default")
      (node (ref "R27") (pin "1") (pinfunction "1_1") (pintype "passive"))
      (node (ref "XP5") (pin "9") (pinfunction "9_9") (pintype "passive"))
    )
    (net (code "93") (name "Net-(R28-Pad1)") (class "Default")
      (node (ref "R28") (pin "1") (pinfunction "1_1") (pintype "passive"))
      (node (ref "XP5") (pin "8") (pinfunction "8_8") (pintype "passive"))
    )
    (net (code "94") (name "Net-(R29-Pad1)") (class "Default")
      (node (ref "R29") (pin "1") (pinfunction "1_1") (pintype "passive"))
      (node (ref "XP5") (pin "3") (pinfunction "3_3") (pintype "passive"))
    )
    (net (code "95") (name "Net-(R30-Pad1)") (class "Default")
      (node (ref "R30") (pin "1") (pinfunction "1_1") (pintype "passive"))
      (node (ref "XP5") (pin "2") (pinfunction "2_2") (pintype "passive"))
    )
    (net (code "96") (name "Net-(R31-Pad1)") (class "Default")
      (node (ref "R31") (pin "1") (pinfunction "1_1") (pintype "passive"))
      (node (ref "XP5") (pin "1") (pinfunction "1_1") (pintype "passive"))
    )
    (net (code "97") (name "Net-(R32-Pad1)") (class "Default")
      (node (ref "R32") (pin "1") (pinfunction "1_1") (pintype "passive"))
      (node (ref "XP5") (pin "4") (pinfunction "4_4") (pintype "passive"))
    )
    (net (code "98") (name "unconnected-(D5-I8-Pad8)") (class "Default")
      (node (ref "D5") (pin "8") (pinfunction "I8_8") (pintype "passive"))
    )
    (net (code "99") (name "unconnected-(D5-O8-Pad11)") (class "Default")
      (node (ref "D5") (pin "11") (pinfunction "O8_11") (pintype "passive"))
    )
    (net (code "100") (name "unconnected-(D8-I8-Pad8)") (class "Default")
      (node (ref "D8") (pin "8") (pinfunction "I8_8") (pintype "passive"))
    )
    (net (code "101") (name "unconnected-(D8-O8-Pad11)") (class "Default")
      (node (ref "D8") (pin "11") (pinfunction "O8_11") (pintype "passive"))
    )
    (net (code "102") (name "unconnected-(XP4-Pad17)") (class "Default")
      (node (ref "XP4") (pin "17") (pinfunction "17_17") (pintype "passive"))
    )
    (net (code "103") (name "unconnected-(XP4-Pad24)") (class "Default")
      (node (ref "XP4") (pin "24") (pinfunction "24_24") (pintype "passive"))
    )
    (net (code "104") (name "unconnected-(XP4-Pad26)") (class "Default")
      (node (ref "XP4") (pin "26") (pinfunction "26_26") (pintype "passive"))
    )
    (net (code "105") (name "unconnected-(XP4-Pad27)") (class "Default")
      (node (ref "XP4") (pin "27") (pinfunction "27_27") (pintype "passive"))
    )
    (net (code "106") (name "unconnected-(XP4-Pad28)") (class "Default")
      (node (ref "XP4") (pin "28") (pinfunction "28_28") (pintype "passive"))
    )
    (net (code "107") (name "unconnected-(XP4-Pad32)") (class "Default")
      (node (ref "XP4") (pin "32") (pinfunction "32_32") (pintype "passive"))
    )
    (net (code "108") (name "unconnected-(XP5-Pad6)") (class "Default")
      (node (ref "XP5") (pin "6") (pinfunction "6_6") (pintype "passive"))
    )
    (net (code "109") (name "unconnected-(XP5-Pad7)") (class "Default")
      (node (ref "XP5") (pin "7") (pinfunction "7_7") (pintype "passive"))
    )
  )
)
